# Mezclador2.net
KiCad netlist of a schematic drawn in Altium Designer
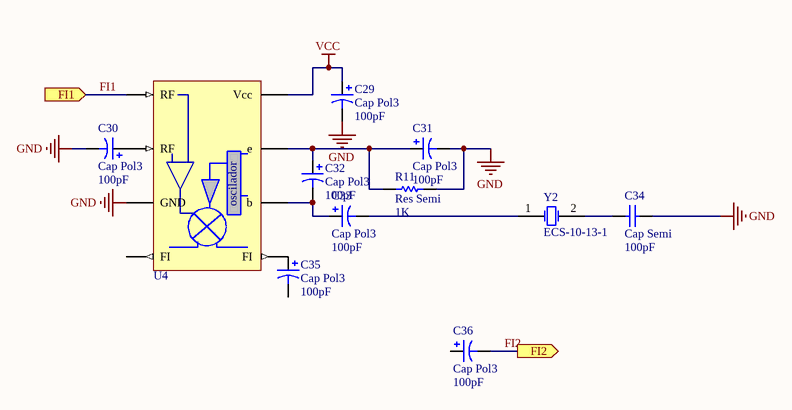
[diagram p0: Mezclador2.SchDoc]

(export (version "E")
  (design (tool "Eeschema 10.0.6"))
  (components
    (comp (ref "C29")
      (value "Cap Pol3")
      (footprint "C0805")
      (description "Polarized Capacitor (Surface Mount)")
      (fields (field (name "ALTIUM_VALUE") "100pF") (field (name "PUBLISHER") "Altium Limited"))
      (libsource (lib "Miscellaneous Devices") (part "Cap Pol3"))
    )
    (comp (ref "C30")
      (value "Cap Pol3")
      (footprint "C0805")
      (description "Polarized Capacitor (Surface Mount)")
      (fields (field (name "ALTIUM_VALUE") "100pF") (field (name "PUBLISHER") "Altium Limited"))
      (libsource (lib "Miscellaneous Devices") (part "Cap Pol3"))
    )
    (comp (ref "C31")
      (value "Cap Pol3")
      (footprint "C0805")
      (description "Polarized Capacitor (Surface Mount)")
      (fields (field (name "ALTIUM_VALUE") "100pF") (field (name "PUBLISHER") "Altium Limited"))
      (libsource (lib "Miscellaneous Devices") (part "Cap Pol3"))
    )
    (comp (ref "C32")
      (value "Cap Pol3")
      (footprint "C0805")
      (description "Polarized Capacitor (Surface Mount)")
      (fields (field (name "ALTIUM_VALUE") "100pF") (field (name "PUBLISHER") "Altium Limited"))
      (libsource (lib "Miscellaneous Devices") (part "Cap Pol3"))
    )
    (comp (ref "C33")
      (value "Cap Pol3")
      (footprint "C0805")
      (description "Polarized Capacitor (Surface Mount)")
      (fields (field (name "ALTIUM_VALUE") "100pF") (field (name "PUBLISHER") "Altium Limited"))
      (libsource (lib "Miscellaneous Devices") (part "Cap Pol3"))
    )
    (comp (ref "C34")
      (value "Cap Semi")
      (footprint "C1206")
      (description "Capacitor (Semiconductor SIM Model)")
      (fields (field (name "ALTIUM_VALUE") "100pF") (field (name "PUBLISHER") "Altium Limited"))
      (libsource (lib "Miscellaneous Devices") (part "Cap Semi"))
    )
    (comp (ref "C35")
      (value "Cap Pol3")
      (footprint "C0805")
      (description "Polarized Capacitor (Surface Mount)")
      (fields (field (name "ALTIUM_VALUE") "100pF") (field (name "PUBLISHER") "Altium Limited"))
      (libsource (lib "Miscellaneous Devices") (part "Cap Pol3"))
    )
    (comp (ref "C36")
      (value "Cap Pol3")
      (footprint "C0805")
      (description "Polarized Capacitor (Surface Mount)")
      (fields (field (name "ALTIUM_VALUE") "100pF") (field (name "PUBLISHER") "Altium Limited"))
      (libsource (lib "Miscellaneous Devices") (part "Cap Pol3"))
    )
    (comp (ref "R11")
      (value "Res Semi")
      (footprint "2012[0805]")
      (description "Semiconductor Resistor")
      (fields (field (name "ALTIUM_VALUE") "1K") (field (name "PUBLISHER") "Altium Limited"))
      (libsource (lib "Miscellaneous Devices") (part "Res Semi"))
    )
    (comp (ref "U4")
      (value "SA602")
      (footprint "SA602")
      (description "Mezclador 500MHz")
      (libsource (lib "epf") (part "SA602A"))
    )
    (comp (ref "Y2")
      (value "ECS-10-13-1")
      (footprint "HC-49U")
      (description "Crystal Oscillator")
      (fields (field (name "PUBLISHER") "Altium Limited"))
      (libsource (lib "ECS Crystal Oscillator") (part "ECS-10-13-1"))
    )
  )
  (nets
    (net (code "1") (name "/FI1") (class "Default")
      (node (ref "U4") (pin "1") (pinfunction "RF_1") (pintype "input"))
    )
    (net (code "2") (name "/FI2") (class "Default")
      (node (ref "C36") (pin "2") (pinfunction "2_2") (pintype "passive"))
    )
    (net (code "3") (name "GND") (class "Default")
      (node (ref "C29") (pin "2") (pinfunction "2_2") (pintype "passive"))
      (node (ref "C30") (pin "2") (pinfunction "2_2") (pintype "passive"))
      (node (ref "C31") (pin "2") (pinfunction "2_2") (pintype "passive"))
      (node (ref "C34") (pin "2") (pinfunction "2_2") (pintype "passive"))
      (node (ref "R11") (pin "1") (pinfunction "1_1") (pintype "passive"))
      (node (ref "U4") (pin "3") (pinfunction "GND_3") (pintype "passive"))
    )
    (net (code "4") (name "Net-(C30-Pad1)") (class "Default")
      (node (ref "C30") (pin "1") (pinfunction "1_1") (pintype "passive"))
      (node (ref "U4") (pin "2") (pinfunction "RF_2") (pintype "input"))
    )
    (net (code "5") (name "Net-(C35-Pad1)") (class "Default")
      (node (ref "C35") (pin "1") (pinfunction "1_1") (pintype "passive"))
      (node (ref "U4") (pin "5") (pinfunction "FI_5") (pintype "output"))
    )
    (net (code "6") (name "Net-(U4-b)") (class "Default")
      (node (ref "C32") (pin "2") (pinfunction "2_2") (pintype "passive"))
      (node (ref "C33") (pin "1") (pinfunction "1_1") (pintype "passive"))
      (node (ref "U4") (pin "6") (pinfunction "b_6") (pintype "passive"))
    )
    (net (code "7") (name "Net-(U4-e)") (class "Default")
      (node (ref "C31") (pin "1") (pinfunction "1_1") (pintype "passive"))
      (node (ref "C32") (pin "1") (pinfunction "1_1") (pintype "passive"))
      (node (ref "R11") (pin "2") (pinfunction "2_2") (pintype "passive"))
      (node (ref "U4") (pin "7") (pinfunction "e_7") (pintype "passive"))
    )
    (net (code "8") (name "Net-(Y2-OSC1)") (class "Default")
      (node (ref "C33") (pin "2") (pinfunction "2_2") (pintype "passive"))
      (node (ref "Y2") (pin "1") (pinfunction "OSC1_1") (pintype "passive"))
    )
    (net (code "9") (name "Net-(Y2-OSC2)") (class "Default")
      (node (ref "C34") (pin "1") (pinfunction "1_1") (pintype "passive"))
      (node (ref "Y2") (pin "2") (pinfunction "OSC2_2") (pintype "passive"))
    )
    (net (code "10") (name "VCC") (class "Default")
      (node (ref "C29") (pin "1") (pinfunction "1_1") (pintype "passive"))
      (node (ref "U4") (pin "8") (pinfunction "Vcc_8") (pintype "passive"))
    )
    (net (code "11") (name "unconnected-(C35-Pad2)") (class "Default")
      (node (ref "C35") (pin "2") (pinfunction "2_2") (pintype "passive"))
    )
    (net (code "12") (name "unconnected-(C36-Pad1)") (class "Default")
      (node (ref "C36") (pin "1") (pinfunction "1_1") (pintype "passive"))
    )
    (net (code "13") (name "unconnected-(U4-FI-Pad4)") (class "Default")
      (node (ref "U4") (pin "4") (pinfunction "FI_4") (pintype "output"))
    )
  )
)
